# bldc.net
KiCad netlist of a schematic drawn in EAGLE
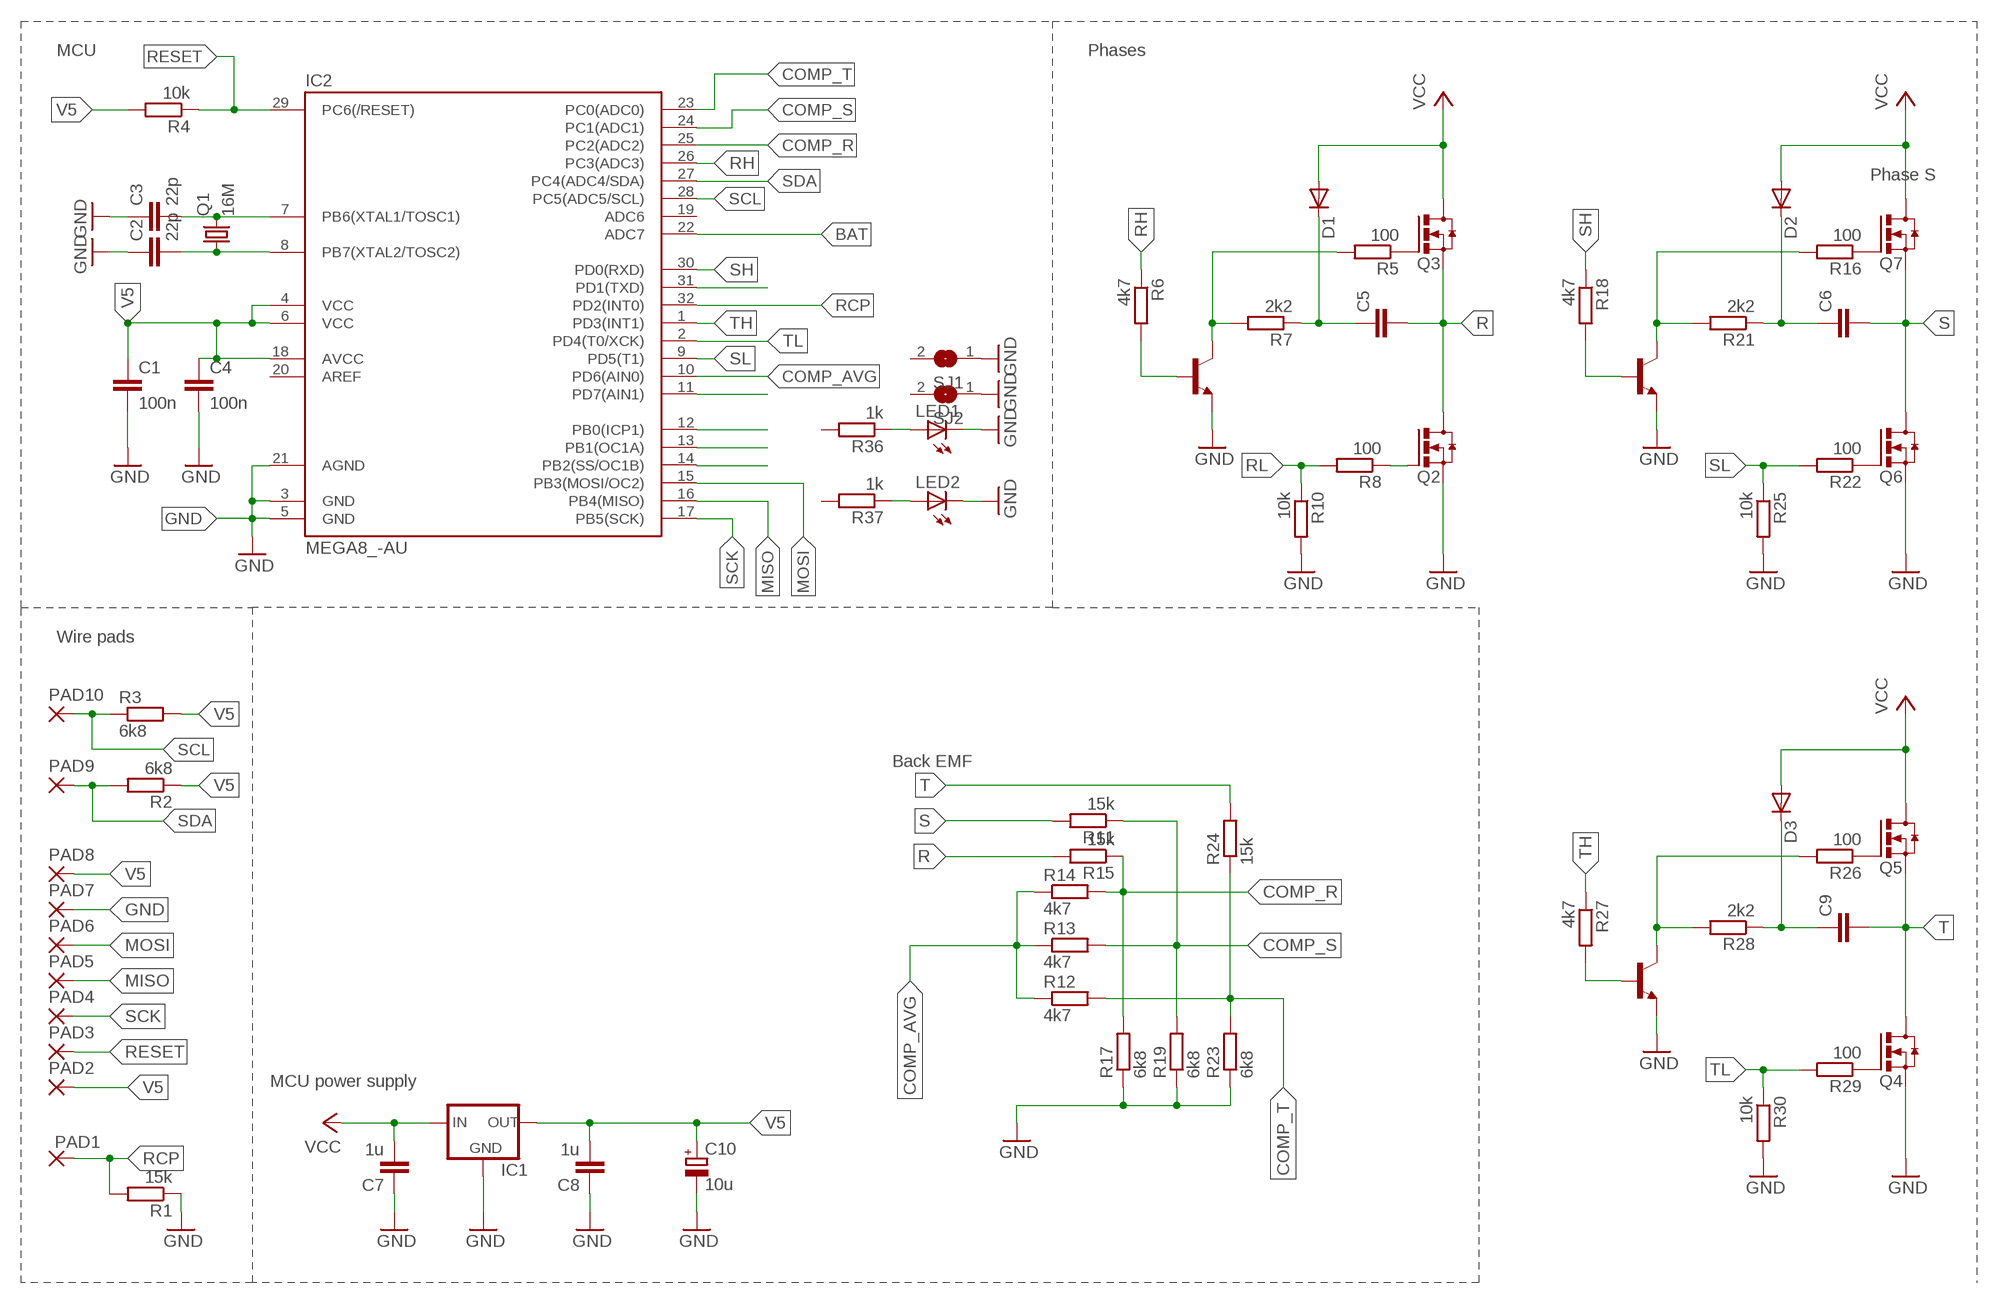
[diagram p0: schematic, sheet 1]

(export (version "E")
  (design (tool "Eeschema 10.0.6"))
  (components
    (comp (ref "C1")
      (value "100n")
      (footprint "eagle-import:C0805K")
      (libsource (lib "eagle-import") (part "rcl2_C-EUC0805K"))
    )
    (comp (ref "C2")
      (value "22p")
      (footprint "eagle-import:C0805K")
      (libsource (lib "eagle-import") (part "rcl2_C-EUC0805K"))
    )
    (comp (ref "C3")
      (value "22p")
      (footprint "eagle-import:C0805K")
      (libsource (lib "eagle-import") (part "rcl2_C-EUC0805K"))
    )
    (comp (ref "C4")
      (value "100n")
      (footprint "eagle-import:C0805K")
      (libsource (lib "eagle-import") (part "rcl2_C-EUC0805K"))
    )
    (comp (ref "C5")
      (value "C-EUC1206K")
      (footprint "eagle-import:C1206K")
      (libsource (lib "eagle-import") (part "C-EUC1206K"))
    )
    (comp (ref "C6")
      (value "C-EUC1206K")
      (footprint "eagle-import:C1206K")
      (libsource (lib "eagle-import") (part "C-EUC1206K"))
    )
    (comp (ref "C7")
      (value "1u")
      (footprint "eagle-import:C0805K")
      (libsource (lib "eagle-import") (part "rcl2_C-EUC0805K"))
    )
    (comp (ref "C8")
      (value "1u")
      (footprint "eagle-import:C0805K")
      (libsource (lib "eagle-import") (part "rcl2_C-EUC0805K"))
    )
    (comp (ref "C9")
      (value "C-EUC1206K")
      (footprint "eagle-import:C1206K")
      (libsource (lib "eagle-import") (part "C-EUC1206K"))
    )
    (comp (ref "C10")
      (value "10u")
      (footprint "eagle-import:E2,5RE")
      (libsource (lib "eagle-import") (part "CPOL-EUE2.5-4V"))
    )
    (comp (ref "D1")
      (value "1N4148SOD-80")
      (footprint "eagle-import:C1206K")
      (libsource (lib "eagle-import") (part "1N4148SOD-80"))
    )
    (comp (ref "D2")
      (value "1N4148SOD-80")
      (footprint "eagle-import:C1206K")
      (libsource (lib "eagle-import") (part "1N4148SOD-80"))
    )
    (comp (ref "D3")
      (value "1N4148SOD-80")
      (footprint "eagle-import:C1206K")
      (libsource (lib "eagle-import") (part "1N4148SOD-80"))
    )
    (comp (ref "IC1")
      (value "LM1117TO252")
      (footprint "eagle-import:TO252")
      (libsource (lib "eagle-import") (part "LM1117TO252"))
    )
    (comp (ref "IC2")
      (value "MEGA8_-AU")
      (footprint "eagle-import:TQFP32-08")
      (libsource (lib "eagle-import") (part "MEGA8_-AU"))
    )
    (comp (ref "LED1")
      (value "LEDCHIPLED_0805")
      (footprint "eagle-import:CHIPLED_0805")
      (libsource (lib "eagle-import") (part "LEDCHIPLED_0805"))
    )
    (comp (ref "LED2")
      (value "LEDCHIPLED_0805")
      (footprint "eagle-import:CHIPLED_0805")
      (libsource (lib "eagle-import") (part "LEDCHIPLED_0805"))
    )
    (comp (ref "PAD1")
      (value "WIREPADSMD1,27-254")
      (footprint "eagle-import:SMD1,27-2,54")
      (libsource (lib "eagle-import") (part "WIREPADSMD1,27-254"))
    )
    (comp (ref "PAD2")
      (value "WIREPADSMD1,27-254")
      (footprint "eagle-import:SMD1,27-2,54")
      (libsource (lib "eagle-import") (part "WIREPADSMD1,27-254"))
    )
    (comp (ref "PAD3")
      (value "WIREPADSMD1,27-254")
      (footprint "eagle-import:SMD1,27-2,54")
      (libsource (lib "eagle-import") (part "WIREPADSMD1,27-254"))
    )
    (comp (ref "PAD4")
      (value "WIREPADSMD1,27-254")
      (footprint "eagle-import:SMD1,27-2,54")
      (libsource (lib "eagle-import") (part "WIREPADSMD1,27-254"))
    )
    (comp (ref "PAD5")
      (value "WIREPADSMD1,27-254")
      (footprint "eagle-import:SMD1,27-2,54")
      (libsource (lib "eagle-import") (part "WIREPADSMD1,27-254"))
    )
    (comp (ref "PAD6")
      (value "WIREPADSMD1,27-254")
      (footprint "eagle-import:SMD1,27-2,54")
      (libsource (lib "eagle-import") (part "WIREPADSMD1,27-254"))
    )
    (comp (ref "PAD7")
      (value "WIREPADSMD1,27-254")
      (footprint "eagle-import:SMD1,27-2,54")
      (libsource (lib "eagle-import") (part "WIREPADSMD1,27-254"))
    )
    (comp (ref "PAD8")
      (value "WIREPADSMD1,27-254")
      (footprint "eagle-import:SMD1,27-2,54")
      (libsource (lib "eagle-import") (part "WIREPADSMD1,27-254"))
    )
    (comp (ref "PAD9")
      (value "WIREPADSMD1,27-254")
      (footprint "eagle-import:SMD1,27-2,54")
      (libsource (lib "eagle-import") (part "WIREPADSMD1,27-254"))
    )
    (comp (ref "PAD10")
      (value "WIREPADSMD1,27-254")
      (footprint "eagle-import:SMD1,27-2,54")
      (libsource (lib "eagle-import") (part "WIREPADSMD1,27-254"))
    )
    (comp (ref "Q1")
      (value "16M")
      (footprint "eagle-import:SM49")
      (libsource (lib "eagle-import") (part "CRYSTALSM49"))
    )
    (comp (ref "Q2")
      (value "IRFR1205")
      (footprint "eagle-import:D-PAK_TO252AA")
      (libsource (lib "eagle-import") (part "IRFR1205"))
    )
    (comp (ref "Q3")
      (value "IRFR1205")
      (footprint "eagle-import:D-PAK_TO252AA")
      (libsource (lib "eagle-import") (part "IRFR1205"))
    )
    (comp (ref "Q4")
      (value "IRFR1205")
      (footprint "eagle-import:D-PAK_TO252AA")
      (libsource (lib "eagle-import") (part "IRFR1205"))
    )
    (comp (ref "Q5")
      (value "IRFR1205")
      (footprint "eagle-import:D-PAK_TO252AA")
      (libsource (lib "eagle-import") (part "IRFR1205"))
    )
    (comp (ref "Q6")
      (value "IRFR1205")
      (footprint "eagle-import:D-PAK_TO252AA")
      (libsource (lib "eagle-import") (part "IRFR1205"))
    )
    (comp (ref "Q7")
      (value "IRFR1205")
      (footprint "eagle-import:D-PAK_TO252AA")
      (libsource (lib "eagle-import") (part "IRFR1205"))
    )
    (comp (ref "R1")
      (value "15k")
      (footprint "eagle-import:R0603")
      (libsource (lib "eagle-import") (part "resistor_R-EU_R0603"))
    )
    (comp (ref "R2")
      (value "6k8")
      (footprint "eagle-import:R0603")
      (libsource (lib "eagle-import") (part "resistor_R-EU_R0603"))
    )
    (comp (ref "R3")
      (value "6k8")
      (footprint "eagle-import:R0603")
      (libsource (lib "eagle-import") (part "resistor_R-EU_R0603"))
    )
    (comp (ref "R4")
      (value "10k")
      (footprint "eagle-import:R0603")
      (libsource (lib "eagle-import") (part "resistor_R-EU_R0603"))
    )
    (comp (ref "R5")
      (value "100")
      (footprint "eagle-import:R0603")
      (libsource (lib "eagle-import") (part "resistor_R-EU_R0603"))
    )
    (comp (ref "R6")
      (value "4k7")
      (footprint "eagle-import:R0603")
      (libsource (lib "eagle-import") (part "resistor_R-EU_R0603"))
    )
    (comp (ref "R7")
      (value "2k2")
      (footprint "eagle-import:R0603")
      (libsource (lib "eagle-import") (part "resistor_R-EU_R0603"))
    )
    (comp (ref "R8")
      (value "100")
      (footprint "eagle-import:R0603")
      (libsource (lib "eagle-import") (part "resistor_R-EU_R0603"))
    )
    (comp (ref "R10")
      (value "10k")
      (footprint "eagle-import:R0603")
      (libsource (lib "eagle-import") (part "resistor_R-EU_R0603"))
    )
    (comp (ref "R11")
      (value "15k")
      (footprint "eagle-import:R0603")
      (libsource (lib "eagle-import") (part "resistor_R-EU_R0603"))
    )
    (comp (ref "R12")
      (value "4k7")
      (footprint "eagle-import:R0603")
      (libsource (lib "eagle-import") (part "resistor_R-EU_R0603"))
    )
    (comp (ref "R13")
      (value "4k7")
      (footprint "eagle-import:R0603")
      (libsource (lib "eagle-import") (part "resistor_R-EU_R0603"))
    )
    (comp (ref "R14")
      (value "4k7")
      (footprint "eagle-import:R0603")
      (libsource (lib "eagle-import") (part "resistor_R-EU_R0603"))
    )
    (comp (ref "R15")
      (value "15k")
      (footprint "eagle-import:R0805")
      (libsource (lib "eagle-import") (part "R-EU_R0805"))
    )
    (comp (ref "R16")
      (value "100")
      (footprint "eagle-import:R0603")
      (libsource (lib "eagle-import") (part "resistor_R-EU_R0603"))
    )
    (comp (ref "R17")
      (value "6k8")
      (footprint "eagle-import:R0603")
      (libsource (lib "eagle-import") (part "resistor_R-EU_R0603"))
    )
    (comp (ref "R18")
      (value "4k7")
      (footprint "eagle-import:R0603")
      (libsource (lib "eagle-import") (part "resistor_R-EU_R0603"))
    )
    (comp (ref "R19")
      (value "6k8")
      (footprint "eagle-import:R0603")
      (libsource (lib "eagle-import") (part "resistor_R-EU_R0603"))
    )
    (comp (ref "R21")
      (value "2k2")
      (footprint "eagle-import:R0603")
      (libsource (lib "eagle-import") (part "resistor_R-EU_R0603"))
    )
    (comp (ref "R22")
      (value "100")
      (footprint "eagle-import:R0603")
      (libsource (lib "eagle-import") (part "resistor_R-EU_R0603"))
    )
    (comp (ref "R23")
      (value "6k8")
      (footprint "eagle-import:R0603")
      (libsource (lib "eagle-import") (part "resistor_R-EU_R0603"))
    )
    (comp (ref "R24")
      (value "15k")
      (footprint "eagle-import:R0603")
      (libsource (lib "eagle-import") (part "resistor_R-EU_R0603"))
    )
    (comp (ref "R25")
      (value "10k")
      (footprint "eagle-import:R0603")
      (libsource (lib "eagle-import") (part "resistor_R-EU_R0603"))
    )
    (comp (ref "R26")
      (value "100")
      (footprint "eagle-import:R0603")
      (libsource (lib "eagle-import") (part "resistor_R-EU_R0603"))
    )
    (comp (ref "R27")
      (value "4k7")
      (footprint "eagle-import:R0603")
      (libsource (lib "eagle-import") (part "resistor_R-EU_R0603"))
    )
    (comp (ref "R28")
      (value "2k2")
      (footprint "eagle-import:R0603")
      (libsource (lib "eagle-import") (part "resistor_R-EU_R0603"))
    )
    (comp (ref "R29")
      (value "100")
      (footprint "eagle-import:R0603")
      (libsource (lib "eagle-import") (part "resistor_R-EU_R0603"))
    )
    (comp (ref "R30")
      (value "10k")
      (footprint "eagle-import:R0603")
      (libsource (lib "eagle-import") (part "resistor_R-EU_R0603"))
    )
    (comp (ref "R36")
      (value "1k")
      (footprint "eagle-import:R0603")
      (libsource (lib "eagle-import") (part "resistor_R-EU_R0603"))
    )
    (comp (ref "R37")
      (value "1k")
      (footprint "eagle-import:R0603")
      (libsource (lib "eagle-import") (part "resistor_R-EU_R0603"))
    )
    (comp (ref "SJ1") (value "SJ") (footprint "eagle-import:SJ") (libsource (lib "eagle-import") (part "SJ")))
    (comp (ref "SJ2") (value "SJ") (footprint "eagle-import:SJ") (libsource (lib "eagle-import") (part "SJ")))
    (comp (ref "T1")
      (value "BC847")
      (footprint "eagle-import:SOT23")
      (libsource (lib "eagle-import") (part "BC847"))
    )
    (comp (ref "T2")
      (value "BC847")
      (footprint "eagle-import:SOT23")
      (libsource (lib "eagle-import") (part "BC847"))
    )
    (comp (ref "T3")
      (value "BC847")
      (footprint "eagle-import:SOT23")
      (libsource (lib "eagle-import") (part "BC847"))
    )
  )
  (nets
    (net (code "1") (name "BAT") (class "Default")
      (node (ref "IC2") (pin "22") (pinfunction "ADC7_22") (pintype "passive"))
    )
    (net (code "2") (name "COMP_AVG") (class "Default")
      (node (ref "IC2") (pin "10") (pinfunction "PD6(AIN0)_10") (pintype "bidirectional"))
      (node (ref "R12") (pin "1") (pinfunction "1_1") (pintype "passive"))
      (node (ref "R13") (pin "1") (pinfunction "1_1") (pintype "passive"))
      (node (ref "R14") (pin "1") (pinfunction "1_1") (pintype "passive"))
    )
    (net (code "3") (name "COMP_R") (class "Default")
      (node (ref "IC2") (pin "25") (pinfunction "PC2(ADC2)_25") (pintype "bidirectional"))
      (node (ref "R14") (pin "2") (pinfunction "2_2") (pintype "passive"))
      (node (ref "R15") (pin "1") (pinfunction "1_1") (pintype "passive"))
      (node (ref "R17") (pin "2") (pinfunction "2_2") (pintype "passive"))
    )
    (net (code "4") (name "COMP_S") (class "Default")
      (node (ref "IC2") (pin "24") (pinfunction "PC1(ADC1)_24") (pintype "bidirectional"))
      (node (ref "R11") (pin "1") (pinfunction "1_1") (pintype "passive"))
      (node (ref "R13") (pin "2") (pinfunction "2_2") (pintype "passive"))
      (node (ref "R19") (pin "2") (pinfunction "2_2") (pintype "passive"))
    )
    (net (code "5") (name "COMP_T") (class "Default")
      (node (ref "IC2") (pin "23") (pinfunction "PC0(ADC0)_23") (pintype "bidirectional"))
      (node (ref "R12") (pin "2") (pinfunction "2_2") (pintype "passive"))
      (node (ref "R23") (pin "2") (pinfunction "2_2") (pintype "passive"))
      (node (ref "R24") (pin "1") (pinfunction "1_1") (pintype "passive"))
    )
    (net (code "6") (name "GND") (class "Default")
      (node (ref "C1") (pin "2") (pinfunction "2_2") (pintype "passive"))
      (node (ref "C10") (pin "-") (pinfunction "-_-") (pintype "passive"))
      (node (ref "C2") (pin "1") (pinfunction "1_1") (pintype "passive"))
      (node (ref "C3") (pin "1") (pinfunction "1_1") (pintype "passive"))
      (node (ref "C4") (pin "2") (pinfunction "2_2") (pintype "passive"))
      (node (ref "C7") (pin "1") (pinfunction "1_1") (pintype "passive"))
      (node (ref "C8") (pin "1") (pinfunction "1_1") (pintype "passive"))
      (node (ref "IC1") (pin "1") (pinfunction "GND_1") (pintype "input"))
      (node (ref "IC2") (pin "21") (pinfunction "AGND_21") (pintype "power_in"))
      (node (ref "IC2") (pin "3") (pinfunction "GND_3") (pintype "power_in"))
      (node (ref "IC2") (pin "5") (pinfunction "GND_5") (pintype "power_in"))
      (node (ref "LED1") (pin "C") (pinfunction "C_C") (pintype "passive"))
      (node (ref "LED2") (pin "C") (pinfunction "C_C") (pintype "passive"))
      (node (ref "PAD7") (pin "1") (pinfunction "P_1") (pintype "passive"))
      (node (ref "Q2") (pin "3") (pinfunction "S_3") (pintype "passive"))
      (node (ref "Q4") (pin "3") (pinfunction "S_3") (pintype "passive"))
      (node (ref "Q6") (pin "3") (pinfunction "S_3") (pintype "passive"))
      (node (ref "R1") (pin "1") (pinfunction "1_1") (pintype "passive"))
      (node (ref "R10") (pin "2") (pinfunction "2_2") (pintype "passive"))
      (node (ref "R17") (pin "1") (pinfunction "1_1") (pintype "passive"))
      (node (ref "R19") (pin "1") (pinfunction "1_1") (pintype "passive"))
      (node (ref "R23") (pin "1") (pinfunction "1_1") (pintype "passive"))
      (node (ref "R25") (pin "2") (pinfunction "2_2") (pintype "passive"))
      (node (ref "R30") (pin "2") (pinfunction "2_2") (pintype "passive"))
      (node (ref "SJ1") (pin "1") (pinfunction "1_1") (pintype "passive"))
      (node (ref "SJ2") (pin "1") (pinfunction "1_1") (pintype "passive"))
      (node (ref "T1") (pin "2") (pinfunction "E_2") (pintype "passive"))
      (node (ref "T2") (pin "2") (pinfunction "E_2") (pintype "passive"))
      (node (ref "T3") (pin "2") (pinfunction "E_2") (pintype "passive"))
    )
    (net (code "7") (name "MISO") (class "Default")
      (node (ref "IC2") (pin "16") (pinfunction "PB4(MISO)_16") (pintype "bidirectional"))
      (node (ref "PAD5") (pin "1") (pinfunction "P_1") (pintype "passive"))
    )
    (net (code "8") (name "MOSI") (class "Default")
      (node (ref "IC2") (pin "15") (pinfunction "PB3(MOSI/OC2)_15") (pintype "bidirectional"))
      (node (ref "PAD6") (pin "1") (pinfunction "P_1") (pintype "passive"))
    )
    (net (code "9") (name "Net-(D1-C)") (class "Default")
      (node (ref "C5") (pin "1") (pinfunction "1_1") (pintype "passive"))
      (node (ref "D1") (pin "2") (pinfunction "C_2") (pintype "passive"))
      (node (ref "R7") (pin "1") (pinfunction "1_1") (pintype "passive"))
    )
    (net (code "10") (name "Net-(D2-C)") (class "Default")
      (node (ref "C6") (pin "1") (pinfunction "1_1") (pintype "passive"))
      (node (ref "D2") (pin "2") (pinfunction "C_2") (pintype "passive"))
      (node (ref "R21") (pin "1") (pinfunction "1_1") (pintype "passive"))
    )
    (net (code "11") (name "Net-(D3-C)") (class "Default")
      (node (ref "C9") (pin "1") (pinfunction "1_1") (pintype "passive"))
      (node (ref "D3") (pin "2") (pinfunction "C_2") (pintype "passive"))
      (node (ref "R28") (pin "1") (pinfunction "1_1") (pintype "passive"))
    )
    (net (code "12") (name "Net-(IC2-PB6(XTAL1{slash}TOSC1))") (class "Default")
      (node (ref "C3") (pin "2") (pinfunction "2_2") (pintype "passive"))
      (node (ref "IC2") (pin "7") (pinfunction "PB6(XTAL1/TOSC1)_7") (pintype "bidirectional"))
      (node (ref "Q1") (pin "2") (pinfunction "2_2") (pintype "passive"))
    )
    (net (code "13") (name "Net-(IC2-PB7(XTAL2{slash}TOSC2))") (class "Default")
      (node (ref "C2") (pin "2") (pinfunction "2_2") (pintype "passive"))
      (node (ref "IC2") (pin "8") (pinfunction "PB7(XTAL2/TOSC2)_8") (pintype "bidirectional"))
      (node (ref "Q1") (pin "1") (pinfunction "1_1") (pintype "passive"))
    )
    (net (code "14") (name "Net-(LED1-PadA)") (class "Default")
      (node (ref "LED1") (pin "A") (pinfunction "A_A") (pintype "passive"))
      (node (ref "R36") (pin "1") (pinfunction "1_1") (pintype "passive"))
    )
    (net (code "15") (name "Net-(LED2-PadA)") (class "Default")
      (node (ref "LED2") (pin "A") (pinfunction "A_A") (pintype "passive"))
      (node (ref "R37") (pin "1") (pinfunction "1_1") (pintype "passive"))
    )
    (net (code "16") (name "Net-(Q2-G)") (class "Default")
      (node (ref "Q2") (pin "1") (pinfunction "G_1") (pintype "passive"))
      (node (ref "R8") (pin "1") (pinfunction "1_1") (pintype "passive"))
    )
    (net (code "17") (name "Net-(Q3-G)") (class "Default")
      (node (ref "Q3") (pin "1") (pinfunction "G_1") (pintype "passive"))
      (node (ref "R5") (pin "1") (pinfunction "1_1") (pintype "passive"))
    )
    (net (code "18") (name "Net-(Q4-G)") (class "Default")
      (node (ref "Q4") (pin "1") (pinfunction "G_1") (pintype "passive"))
      (node (ref "R29") (pin "1") (pinfunction "1_1") (pintype "passive"))
    )
    (net (code "19") (name "Net-(Q5-G)") (class "Default")
      (node (ref "Q5") (pin "1") (pinfunction "G_1") (pintype "passive"))
      (node (ref "R26") (pin "1") (pinfunction "1_1") (pintype "passive"))
    )
    (net (code "20") (name "Net-(Q6-G)") (class "Default")
      (node (ref "Q6") (pin "1") (pinfunction "G_1") (pintype "passive"))
      (node (ref "R22") (pin "1") (pinfunction "1_1") (pintype "passive"))
    )
    (net (code "21") (name "Net-(Q7-G)") (class "Default")
      (node (ref "Q7") (pin "1") (pinfunction "G_1") (pintype "passive"))
      (node (ref "R16") (pin "1") (pinfunction "1_1") (pintype "passive"))
    )
    (net (code "22") (name "Net-(T1-B)") (class "Default")
      (node (ref "R6") (pin "2") (pinfunction "2_2") (pintype "passive"))
      (node (ref "T1") (pin "1") (pinfunction "B_1") (pintype "passive"))
    )
    (net (code "23") (name "Net-(T1-C)") (class "Default")
      (node (ref "R5") (pin "2") (pinfunction "2_2") (pintype "passive"))
      (node (ref "R7") (pin "2") (pinfunction "2_2") (pintype "passive"))
      (node (ref "T1") (pin "3") (pinfunction "C_3") (pintype "passive"))
    )
    (net (code "24") (name "Net-(T2-B)") (class "Default")
      (node (ref "R18") (pin "2") (pinfunction "2_2") (pintype "passive"))
      (node (ref "T2") (pin "1") (pinfunction "B_1") (pintype "passive"))
    )
    (net (code "25") (name "Net-(T2-C)") (class "Default")
      (node (ref "R16") (pin "2") (pinfunction "2_2") (pintype "passive"))
      (node (ref "R21") (pin "2") (pinfunction "2_2") (pintype "passive"))
      (node (ref "T2") (pin "3") (pinfunction "C_3") (pintype "passive"))
    )
    (net (code "26") (name "Net-(T3-B)") (class "Default")
      (node (ref "R27") (pin "2") (pinfunction "2_2") (pintype "passive"))
      (node (ref "T3") (pin "1") (pinfunction "B_1") (pintype "passive"))
    )
    (net (code "27") (name "Net-(T3-C)") (class "Default")
      (node (ref "R26") (pin "2") (pinfunction "2_2") (pintype "passive"))
      (node (ref "R28") (pin "2") (pinfunction "2_2") (pintype "passive"))
      (node (ref "T3") (pin "3") (pinfunction "C_3") (pintype "passive"))
    )
    (net (code "28") (name "R") (class "Default")
      (node (ref "C5") (pin "2") (pinfunction "2_2") (pintype "passive"))
      (node (ref "Q2") (pin "4") (pinfunction "D_4") (pintype "passive"))
      (node (ref "Q3") (pin "3") (pinfunction "S_3") (pintype "passive"))
      (node (ref "R15") (pin "2") (pinfunction "2_2") (pintype "passive"))
    )
    (net (code "29") (name "RCP") (class "Default")
      (node (ref "IC2") (pin "32") (pinfunction "PD2(INT0)_32") (pintype "bidirectional"))
      (node (ref "PAD1") (pin "1") (pinfunction "P_1") (pintype "passive"))
      (node (ref "R1") (pin "2") (pinfunction "2_2") (pintype "passive"))
    )
    (net (code "30") (name "RESET") (class "Default")
      (node (ref "IC2") (pin "29") (pinfunction "PC6(/RESET)_29") (pintype "bidirectional"))
      (node (ref "PAD3") (pin "1") (pinfunction "P_1") (pintype "passive"))
      (node (ref "R4") (pin "1") (pinfunction "1_1") (pintype "passive"))
    )
    (net (code "31") (name "RH") (class "Default")
      (node (ref "IC2") (pin "26") (pinfunction "PC3(ADC3)_26") (pintype "bidirectional"))
      (node (ref "R6") (pin "1") (pinfunction "1_1") (pintype "passive"))
    )
    (net (code "32") (name "RL") (class "Default")
      (node (ref "R10") (pin "1") (pinfunction "1_1") (pintype "passive"))
      (node (ref "R8") (pin "2") (pinfunction "2_2") (pintype "passive"))
    )
    (net (code "33") (name "S") (class "Default")
      (node (ref "C6") (pin "2") (pinfunction "2_2") (pintype "passive"))
      (node (ref "Q6") (pin "4") (pinfunction "D_4") (pintype "passive"))
      (node (ref "Q7") (pin "3") (pinfunction "S_3") (pintype "passive"))
      (node (ref "R11") (pin "2") (pinfunction "2_2") (pintype "passive"))
    )
    (net (code "34") (name "SCK") (class "Default")
      (node (ref "IC2") (pin "17") (pinfunction "PB5(SCK)_17") (pintype "bidirectional"))
      (node (ref "PAD4") (pin "1") (pinfunction "P_1") (pintype "passive"))
    )
    (net (code "35") (name "SCL") (class "Default")
      (node (ref "IC2") (pin "28") (pinfunction "PC5(ADC5/SCL)_28") (pintype "bidirectional"))
      (node (ref "PAD10") (pin "1") (pinfunction "P_1") (pintype "passive"))
      (node (ref "R3") (pin "1") (pinfunction "1_1") (pintype "passive"))
    )
    (net (code "36") (name "SDA") (class "Default")
      (node (ref "IC2") (pin "27") (pinfunction "PC4(ADC4/SDA)_27") (pintype "bidirectional"))
      (node (ref "PAD9") (pin "1") (pinfunction "P_1") (pintype "passive"))
      (node (ref "R2") (pin "2") (pinfunction "2_2") (pintype "passive"))
    )
    (net (code "37") (name "SH") (class "Default")
      (node (ref "IC2") (pin "30") (pinfunction "PD0(RXD)_30") (pintype "bidirectional"))
      (node (ref "R18") (pin "1") (pinfunction "1_1") (pintype "passive"))
    )
    (net (code "38") (name "SL") (class "Default")
      (node (ref "IC2") (pin "9") (pinfunction "PD5(T1)_9") (pintype "bidirectional"))
      (node (ref "R22") (pin "2") (pinfunction "2_2") (pintype "passive"))
      (node (ref "R25") (pin "1") (pinfunction "1_1") (pintype "passive"))
    )
    (net (code "39") (name "T") (class "Default")
      (node (ref "C9") (pin "2") (pinfunction "2_2") (pintype "passive"))
      (node (ref "Q4") (pin "4") (pinfunction "D_4") (pintype "passive"))
      (node (ref "Q5") (pin "3") (pinfunction "S_3") (pintype "passive"))
      (node (ref "R24") (pin "2") (pinfunction "2_2") (pintype "passive"))
    )
    (net (code "40") (name "TH") (class "Default")
      (node (ref "IC2") (pin "1") (pinfunction "PD3(INT1)_1") (pintype "bidirectional"))
      (node (ref "R27") (pin "1") (pinfunction "1_1") (pintype "passive"))
    )
    (net (code "41") (name "TL") (class "Default")
      (node (ref "IC2") (pin "2") (pinfunction "PD4(T0/XCK)_2") (pintype "bidirectional"))
      (node (ref "R29") (pin "2") (pinfunction "2_2") (pintype "passive"))
      (node (ref "R30") (pin "1") (pinfunction "1_1") (pintype "passive"))
    )
    (net (code "42") (name "V5") (class "Default")
      (node (ref "C1") (pin "1") (pinfunction "1_1") (pintype "passive"))
      (node (ref "C10") (pin "+") (pinfunction "+_+") (pintype "passive"))
      (node (ref "C4") (pin "1") (pinfunction "1_1") (pintype "passive"))
      (node (ref "C8") (pin "2") (pinfunction "2_2") (pintype "passive"))
      (node (ref "IC1") (pin "3") (pinfunction "OUT_3") (pintype "passive"))
      (node (ref "IC2") (pin "18") (pinfunction "AVCC_18") (pintype "passive"))
      (node (ref "IC2") (pin "4") (pinfunction "VCC_4") (pintype "power_in"))
      (node (ref "IC2") (pin "6") (pinfunction "VCC_6") (pintype "power_in"))
      (node (ref "PAD2") (pin "1") (pinfunction "P_1") (pintype "passive"))
      (node (ref "PAD8") (pin "1") (pinfunction "P_1") (pintype "passive"))
      (node (ref "R2") (pin "1") (pinfunction "1_1") (pintype "passive"))
      (node (ref "R3") (pin "2") (pinfunction "2_2") (pintype "passive"))
      (node (ref "R4") (pin "2") (pinfunction "2_2") (pintype "passive"))
    )
    (net (code "43") (name "VCC") (class "Default")
      (node (ref "C7") (pin "2") (pinfunction "2_2") (pintype "passive"))
      (node (ref "D1") (pin "1") (pinfunction "A_1") (pintype "passive"))
      (node (ref "D2") (pin "1") (pinfunction "A_1") (pintype "passive"))
      (node (ref "D3") (pin "1") (pinfunction "A_1") (pintype "passive"))
      (node (ref "IC1") (pin "2") (pinfunction "IN_2") (pintype "input"))
      (node (ref "Q3") (pin "4") (pinfunction "D_4") (pintype "passive"))
      (node (ref "Q5") (pin "4") (pinfunction "D_4") (pintype "passive"))
      (node (ref "Q7") (pin "4") (pinfunction "D_4") (pintype "passive"))
    )
    (net (code "44") (name "unconnected-(IC2-ADC6-Pad19)") (class "Default")
      (node (ref "IC2") (pin "19") (pinfunction "ADC6_19") (pintype "passive"))
    )
    (net (code "45") (name "unconnected-(IC2-AREF-Pad20)") (class "Default")
      (node (ref "IC2") (pin "20") (pinfunction "AREF_20") (pintype "passive"))
    )
    (net (code "46") (name "unconnected-(IC2-PB0(ICP1)-Pad12)") (class "Default")
      (node (ref "IC2") (pin "12") (pinfunction "PB0(ICP1)_12") (pintype "bidirectional"))
    )
    (net (code "47") (name "unconnected-(IC2-PB1(OC1A)-Pad13)") (class "Default")
      (node (ref "IC2") (pin "13") (pinfunction "PB1(OC1A)_13") (pintype "bidirectional"))
    )
    (net (code "48") (name "unconnected-(IC2-PB2(SS{slash}OC1B)-Pad14)") (class "Default")
      (node (ref "IC2") (pin "14") (pinfunction "PB2(SS/OC1B)_14") (pintype "bidirectional"))
    )
    (net (code "49") (name "unconnected-(IC2-PD1(TXD)-Pad31)") (class "Default")
      (node (ref "IC2") (pin "31") (pinfunction "PD1(TXD)_31") (pintype "bidirectional"))
    )
    (net (code "50") (name "unconnected-(IC2-PD7(AIN1)-Pad11)") (class "Default")
      (node (ref "IC2") (pin "11") (pinfunction "PD7(AIN1)_11") (pintype "bidirectional"))
    )
    (net (code "51") (name "unconnected-(R36-Pad2)") (class "Default")
      (node (ref "R36") (pin "2") (pinfunction "2_2") (pintype "passive"))
    )
    (net (code "52") (name "unconnected-(R37-Pad2)") (class "Default")
      (node (ref "R37") (pin "2") (pinfunction "2_2") (pintype "passive"))
    )
    (net (code "53") (name "unconnected-(SJ1-Pad2)") (class "Default")
      (node (ref "SJ1") (pin "2") (pinfunction "2_2") (pintype "passive"))
    )
    (net (code "54") (name "unconnected-(SJ2-Pad2)") (class "Default")
      (node (ref "SJ2") (pin "2") (pinfunction "2_2") (pintype "passive"))
    )
  )
)
